# TopDrivers.net
KiCad netlist of a schematic drawn in Altium Designer
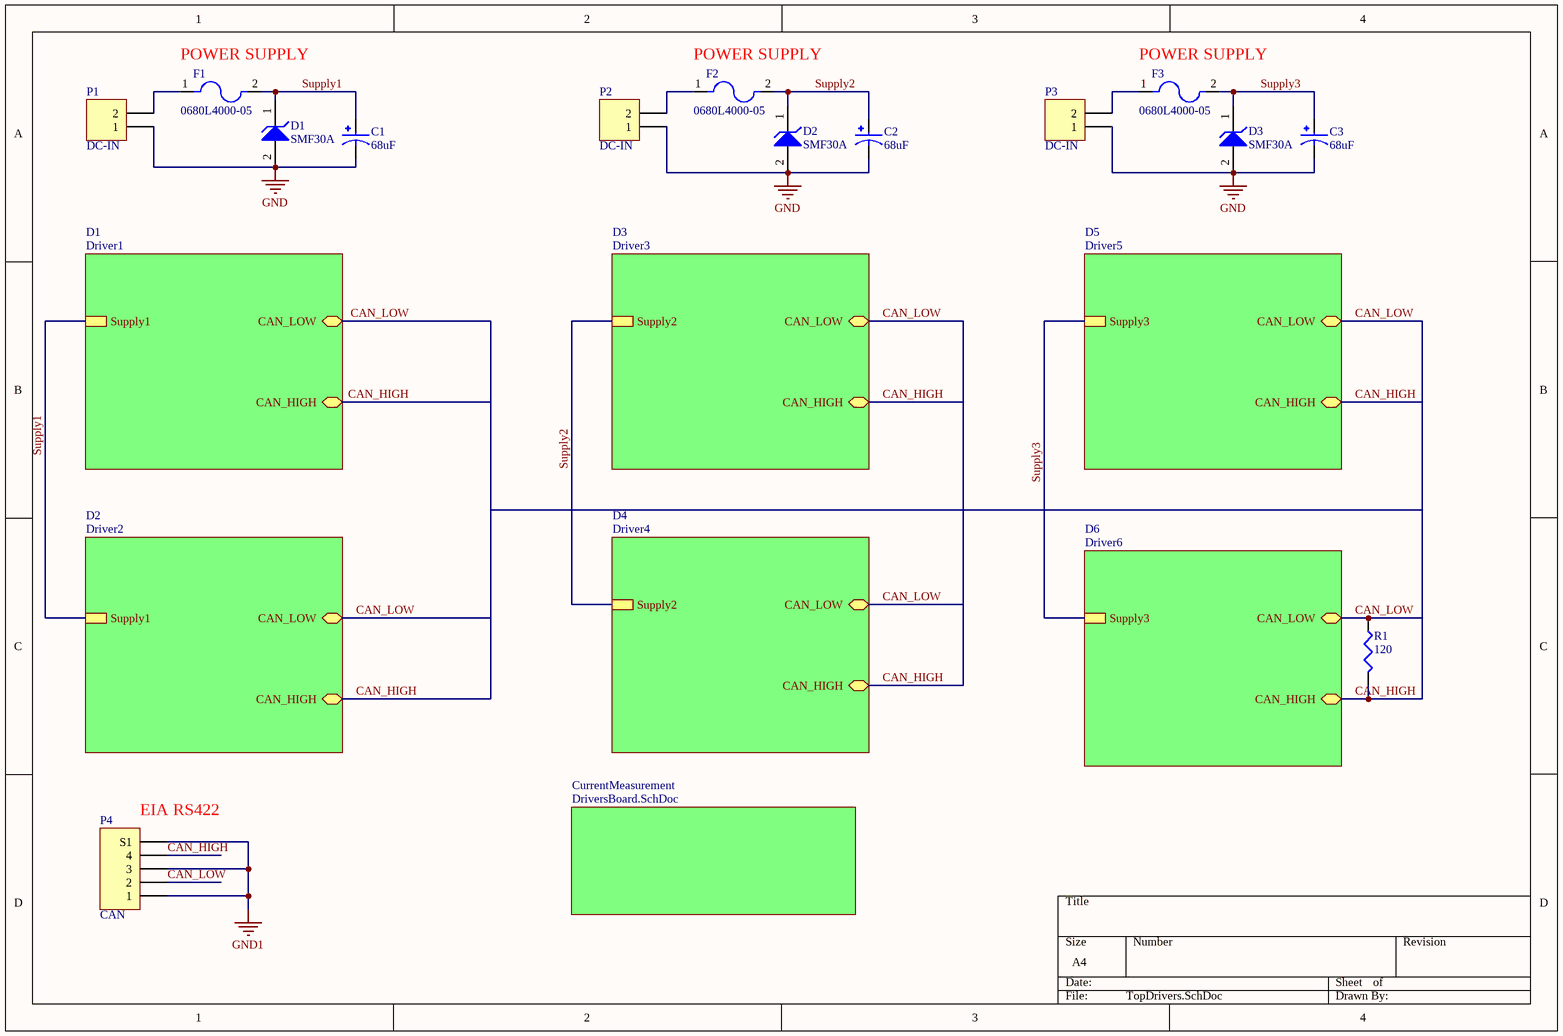
[diagram p0: TopDrivers.SchDoc]

(export (version "E")
  (design (tool "Eeschema 10.0.6"))
  (components
    (comp (ref "C1")
      (value "68uF")
      (footprint "CAP_50SVT68M")
      (fields (field (name "MP") "50SVT68M"))
      (libsource (lib "DriverLib") (part "50SVT68M"))
    )
    (comp (ref "C2")
      (value "68uF")
      (footprint "CAP_50SVT68M")
      (fields (field (name "MP") "50SVT68M"))
      (libsource (lib "DriverLib") (part "50SVT68M"))
    )
    (comp (ref "C3")
      (value "68uF")
      (footprint "CAP_50SVT68M")
      (fields (field (name "MP") "50SVT68M"))
      (libsource (lib "DriverLib") (part "50SVT68M"))
    )
    (comp (ref "D1")
      (value "SMF30A")
      (footprint "ONSC-SOD-123FL-2-498_V")
      (description "200 W Transient Voltage Suppressor, 2-Pin SOD-123FL, Pb-Free, Tape and Reel")
      (fields (field (name "MANUFACTURER") "On Semiconductor") (field (name "PARTNUMBER") "SMF30AT1G"))
      (libsource (lib "SpaceBee") (part "SMF30AT1G"))
    )
    (comp (ref "D2")
      (value "SMF30A")
      (footprint "ONSC-SOD-123FL-2-498_V")
      (description "200 W Transient Voltage Suppressor, 2-Pin SOD-123FL, Pb-Free, Tape and Reel")
      (fields (field (name "MANUFACTURER") "On Semiconductor") (field (name "PARTNUMBER") "SMF30AT1G"))
      (libsource (lib "SpaceBee") (part "SMF30AT1G"))
    )
    (comp (ref "D3")
      (value "SMF30A")
      (footprint "ONSC-SOD-123FL-2-498_V")
      (description "200 W Transient Voltage Suppressor, 2-Pin SOD-123FL, Pb-Free, Tape and Reel")
      (fields (field (name "MANUFACTURER") "On Semiconductor") (field (name "PARTNUMBER") "SMF30AT1G"))
      (libsource (lib "SpaceBee") (part "SMF30AT1G"))
    )
    (comp (ref "F1")
      (value "0680L4000-05")
      (footprint "FUSC6125X279N")
      (description "Surface mount bricks ¦ Silver Plated ¦ 2410 case size ¦ Slow Blow ¦ 4A ¦ Tape and Reel (5000 pcs.)")
      (fields (field (name "MF") "Bel Fuse"))
      (libsource (lib "DriverLib") (part "0680L4000-05"))
    )
    (comp (ref "F2")
      (value "0680L4000-05")
      (footprint "FUSC6125X279N")
      (description "Surface mount bricks ¦ Silver Plated ¦ 2410 case size ¦ Slow Blow ¦ 4A ¦ Tape and Reel (5000 pcs.)")
      (fields (field (name "MF") "Bel Fuse"))
      (libsource (lib "DriverLib") (part "0680L4000-05"))
    )
    (comp (ref "F3")
      (value "0680L4000-05")
      (footprint "FUSC6125X279N")
      (description "Surface mount bricks ¦ Silver Plated ¦ 2410 case size ¦ Slow Blow ¦ 4A ¦ Tape and Reel (5000 pcs.)")
      (fields (field (name "MF") "Bel Fuse"))
      (libsource (lib "DriverLib") (part "0680L4000-05"))
    )
    (comp (ref "P1")
      (value "DC-IN")
      (footprint "MOLEX_1724480002")
      (description "Header, 2-Pin")
      (fields (field (name "PUBLISHER") "Altium Limited"))
      (libsource (lib "SpaceBee") (part "Header 2"))
    )
    (comp (ref "P2")
      (value "DC-IN")
      (footprint "MOLEX_1724480002")
      (description "Header, 2-Pin")
      (fields (field (name "PUBLISHER") "Altium Limited"))
      (libsource (lib "SpaceBee") (part "Header 2"))
    )
    (comp (ref "P3")
      (value "DC-IN")
      (footprint "MOLEX_1724480002")
      (description "Header, 2-Pin")
      (fields (field (name "PUBLISHER") "Altium Limited"))
      (libsource (lib "SpaceBee") (part "Header 2"))
    )
    (comp (ref "P4")
      (value "CAN")
      (footprint "MOLEX_5025850470")
      (description "Header, 5-Pin")
      (fields (field (name "PUBLISHER") "Altium Limited"))
      (libsource (lib "SpaceBee") (part "Header 5"))
    )
    (comp (ref "R1")
      (value "120")
      (footprint "J1-0603")
      (description "Resistor")
      (fields (field (name "Comment") "Res3") (field (name "PUBLISHER") "Altium Limited"))
      (libsource (lib "Miscellaneous Devices") (part "Res3"))
    )
  )
  (nets
    (net (code "1") (name "/CAN_HIGH") (class "Default")
      (node (ref "P4") (pin "4") (pinfunction "4_4") (pintype "passive"))
      (node (ref "R1") (pin "2") (pinfunction "2_2") (pintype "passive"))
    )
    (net (code "2") (name "/CAN_LOW") (class "Default")
      (node (ref "P4") (pin "2") (pinfunction "2_2") (pintype "passive"))
      (node (ref "R1") (pin "1") (pinfunction "1_1") (pintype "passive"))
    )
    (net (code "3") (name "/Supply1") (class "Default")
      (node (ref "C1") (pin "1") (pinfunction "1_1") (pintype "passive"))
      (node (ref "D1") (pin "1") (pinfunction "K_1") (pintype "passive"))
      (node (ref "F1") (pin "2") (pinfunction "2_2") (pintype "passive"))
    )
    (net (code "4") (name "/Supply2") (class "Default")
      (node (ref "C2") (pin "1") (pinfunction "1_1") (pintype "passive"))
      (node (ref "D2") (pin "1") (pinfunction "K_1") (pintype "passive"))
      (node (ref "F2") (pin "2") (pinfunction "2_2") (pintype "passive"))
    )
    (net (code "5") (name "/Supply3") (class "Default")
      (node (ref "C3") (pin "1") (pinfunction "1_1") (pintype "passive"))
      (node (ref "D3") (pin "1") (pinfunction "K_1") (pintype "passive"))
      (node (ref "F3") (pin "2") (pinfunction "2_2") (pintype "passive"))
    )
    (net (code "6") (name "GND") (class "Default")
      (node (ref "C1") (pin "2") (pinfunction "2_2") (pintype "passive"))
      (node (ref "C2") (pin "2") (pinfunction "2_2") (pintype "passive"))
      (node (ref "C3") (pin "2") (pinfunction "2_2") (pintype "passive"))
      (node (ref "D1") (pin "2") (pinfunction "A_2") (pintype "passive"))
      (node (ref "D2") (pin "2") (pinfunction "A_2") (pintype "passive"))
      (node (ref "D3") (pin "2") (pinfunction "A_2") (pintype "passive"))
      (node (ref "P1") (pin "1") (pinfunction "1_1") (pintype "passive"))
      (node (ref "P2") (pin "1") (pinfunction "1_1") (pintype "passive"))
      (node (ref "P3") (pin "1") (pinfunction "1_1") (pintype "passive"))
    )
    (net (code "7") (name "GND1") (class "Default")
      (node (ref "P4") (pin "1") (pinfunction "1_1") (pintype "passive"))
      (node (ref "P4") (pin "3") (pinfunction "3_3") (pintype "passive"))
      (node (ref "P4") (pin "S1") (pinfunction "S1_S1") (pintype "passive"))
    )
    (net (code "8") (name "Net-(F1-Pad1)") (class "Default")
      (node (ref "F1") (pin "1") (pinfunction "1_1") (pintype "passive"))
      (node (ref "P1") (pin "2") (pinfunction "2_2") (pintype "passive"))
    )
    (net (code "9") (name "Net-(F2-Pad1)") (class "Default")
      (node (ref "F2") (pin "1") (pinfunction "1_1") (pintype "passive"))
      (node (ref "P2") (pin "2") (pinfunction "2_2") (pintype "passive"))
    )
    (net (code "10") (name "Net-(F3-Pad1)") (class "Default")
      (node (ref "F3") (pin "1") (pinfunction "1_1") (pintype "passive"))
      (node (ref "P3") (pin "2") (pinfunction "2_2") (pintype "passive"))
    )
  )
)
